# TempSensor-2b.net
KiCad netlist of a schematic drawn in EAGLE
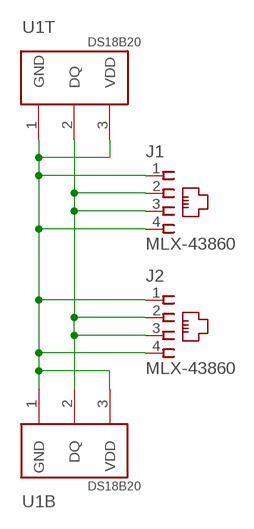
[diagram p0: schematic, sheet 1]

(export (version "E")
  (design (tool "Eeschema 10.0.6"))
  (components
    (comp (ref "J1")
      (value "MLX-43860")
      (footprint "eagle-import:MLX-43860")
      (fields (field (name "MF") "MOLEX"))
      (libsource (lib "eagle-import") (part "MLX-43860"))
    )
    (comp (ref "J2")
      (value "MLX-43860")
      (footprint "eagle-import:MLX-43860")
      (fields (field (name "MF") "MOLEX"))
      (libsource (lib "eagle-import") (part "MLX-43860"))
    )
    (comp (ref "U1B")
      (value "DS18B20")
      (footprint "eagle-import:TO92-")
      (libsource (lib "eagle-import") (part "DS18B20"))
    )
    (comp (ref "U1T")
      (value "DS18B20")
      (footprint "eagle-import:TO92-")
      (libsource (lib "eagle-import") (part "DS18B20"))
    )
  )
  (nets
    (net (code "1") (name "Net-(U1B-DQ)") (class "Default")
      (node (ref "J1") (pin "2") (pinfunction "2_2") (pintype "passive"))
      (node (ref "J1") (pin "3") (pinfunction "3_3") (pintype "passive"))
      (node (ref "J2") (pin "2") (pinfunction "2_2") (pintype "passive"))
      (node (ref "J2") (pin "3") (pinfunction "3_3") (pintype "passive"))
      (node (ref "U1B") (pin "2") (pinfunction "DQ_2") (pintype "bidirectional"))
      (node (ref "U1T") (pin "2") (pinfunction "DQ_2") (pintype "bidirectional"))
    )
    (net (code "2") (name "Net-(U1B-GND)") (class "Default")
      (node (ref "J1") (pin "1") (pinfunction "1_1") (pintype "passive"))
      (node (ref "J1") (pin "4") (pinfunction "4_4") (pintype "passive"))
      (node (ref "J2") (pin "1") (pinfunction "1_1") (pintype "passive"))
      (node (ref "J2") (pin "4") (pinfunction "4_4") (pintype "passive"))
      (node (ref "U1B") (pin "1") (pinfunction "GND_1") (pintype "bidirectional"))
      (node (ref "U1B") (pin "3") (pinfunction "VDD_3") (pintype "bidirectional"))
      (node (ref "U1T") (pin "1") (pinfunction "GND_1") (pintype "bidirectional"))
      (node (ref "U1T") (pin "3") (pinfunction "VDD_3") (pintype "bidirectional"))
    )
  )
)
